# Schematic.net
KiCad netlist of a schematic drawn in EAGLE
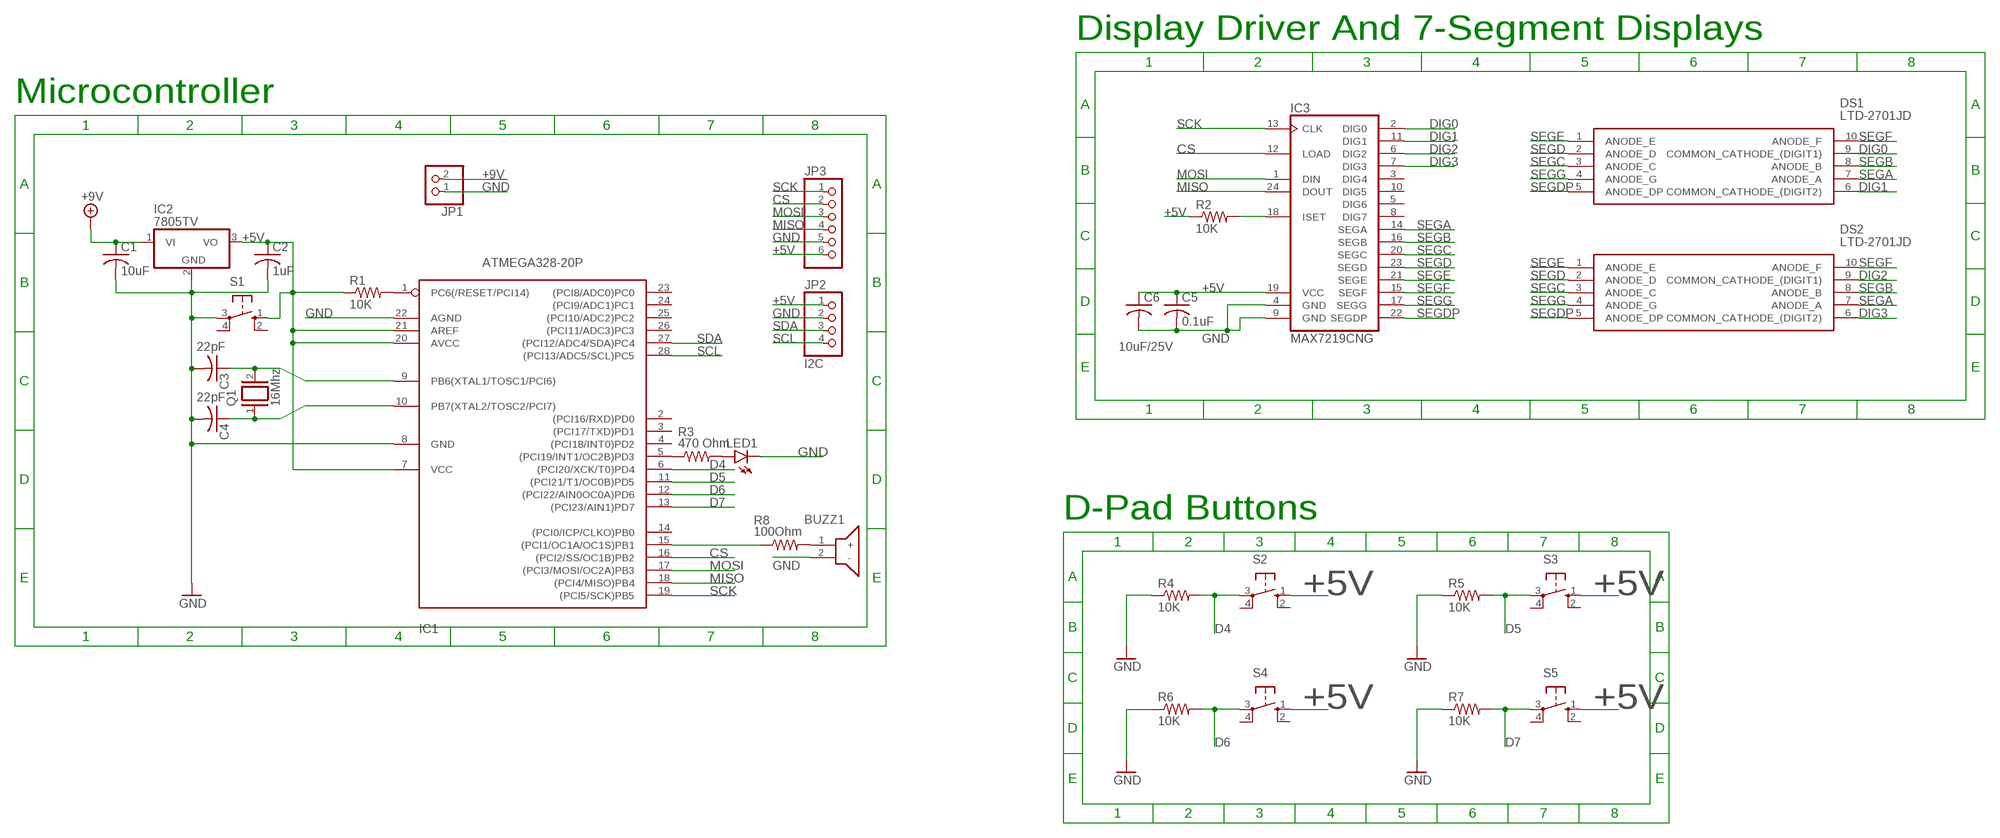
[diagram p0: schematic, sheet 1]

(export (version "E")
  (design (tool "Eeschema 10.0.6"))
  (components
    (comp (ref "BUZZ1")
      (value "CMI-1295-0585T")
      (footprint "eagle-import:CMI12950585T")
      (fields (field (name "MOUSER_PART_NUMBER") "490-CMI-1295-0585T"))
      (libsource (lib "eagle-import") (part "CMI-1295-0585T"))
    )
    (comp (ref "C1")
      (value "10uF")
      (footprint "eagle-import:C1206")
      (libsource (lib "eagle-import") (part "C-USC1206"))
    )
    (comp (ref "C2")
      (value "1uF")
      (footprint "eagle-import:C1206")
      (libsource (lib "eagle-import") (part "C-USC1206"))
    )
    (comp (ref "C3")
      (value "22pF")
      (footprint "eagle-import:C1206")
      (libsource (lib "eagle-import") (part "C-USC1206"))
    )
    (comp (ref "C4")
      (value "22pF")
      (footprint "eagle-import:C1206")
      (libsource (lib "eagle-import") (part "C-USC1206"))
    )
    (comp (ref "C5")
      (value "0.1uF")
      (footprint "eagle-import:C1206")
      (libsource (lib "eagle-import") (part "C-USC1206"))
    )
    (comp (ref "C6")
      (value "10uF/25V")
      (footprint "eagle-import:C1206")
      (libsource (lib "eagle-import") (part "C-USC1206"))
    )
    (comp (ref "DS1")
      (value "LTD-2701JD")
      (footprint "eagle-import:DIPS762W50P254L1502H635Q10N")
      (fields (field (name "MOUSER_PART_NUMBER") "859-LTD-2701JD"))
      (libsource (lib "eagle-import") (part "LTD-2701JD"))
    )
    (comp (ref "DS2")
      (value "LTD-2701JD")
      (footprint "eagle-import:DIPS762W50P254L1502H635Q10N")
      (fields (field (name "MOUSER_PART_NUMBER") "859-LTD-2701JD"))
      (libsource (lib "eagle-import") (part "LTD-2701JD"))
    )
    (comp (ref "IC1")
      (value "ATMEGA328-20P")
      (footprint "eagle-import:DIL28-3")
      (libsource (lib "eagle-import") (part "ATMEGA328P-20"))
    )
    (comp (ref "IC2")
      (value "7805TV")
      (footprint "eagle-import:TO220V")
      (libsource (lib "eagle-import") (part "78TV05"))
    )
    (comp (ref "IC3")
      (value "MAX7219CNG")
      (footprint "eagle-import:DIL24-3")
      (fields (field (name "MF") "MAXIM"))
      (libsource (lib "eagle-import") (part "MAX7219CNG"))
    )
    (comp (ref "JP1")
      (value "PINHD-1X2")
      (footprint "eagle-import:1X02")
      (libsource (lib "eagle-import") (part "PINHD-1X2"))
    )
    (comp (ref "JP2")
      (value "I2C")
      (footprint "eagle-import:1X04")
      (libsource (lib "eagle-import") (part "PINHD-1X4"))
    )
    (comp (ref "JP3")
      (value "PINHD-1X6")
      (footprint "eagle-import:1X06")
      (libsource (lib "eagle-import") (part "PINHD-1X6"))
    )
    (comp (ref "LED1")
      (value "LED5MM")
      (footprint "eagle-import:LED5MM")
      (libsource (lib "eagle-import") (part "LED5MM"))
    )
    (comp (ref "Q1")
      (value "16Mhz")
      (footprint "eagle-import:QS")
      (libsource (lib "eagle-import") (part "XTAL/S"))
    )
    (comp (ref "R1")
      (value "10K")
      (footprint "eagle-import:R1206")
      (libsource (lib "eagle-import") (part "R-US_R1206"))
    )
    (comp (ref "R2")
      (value "10K")
      (footprint "eagle-import:R1206")
      (libsource (lib "eagle-import") (part "R-US_R1206"))
    )
    (comp (ref "R3")
      (value "470 Ohm")
      (footprint "eagle-import:R1206")
      (libsource (lib "eagle-import") (part "R-US_R1206"))
    )
    (comp (ref "R4")
      (value "10K")
      (footprint "eagle-import:R1206")
      (libsource (lib "eagle-import") (part "R-US_R1206"))
    )
    (comp (ref "R5")
      (value "10K")
      (footprint "eagle-import:R1206")
      (libsource (lib "eagle-import") (part "R-US_R1206"))
    )
    (comp (ref "R6")
      (value "10K")
      (footprint "eagle-import:R1206")
      (libsource (lib "eagle-import") (part "R-US_R1206"))
    )
    (comp (ref "R7")
      (value "10K")
      (footprint "eagle-import:R1206")
      (libsource (lib "eagle-import") (part "R-US_R1206"))
    )
    (comp (ref "R8")
      (value "100Ohm")
      (footprint "eagle-import:R1206")
      (libsource (lib "eagle-import") (part "R-US_R1206"))
    )
    (comp (ref "S1")
      (value "10-XX")
      (footprint "eagle-import:B3F-10XX")
      (fields (field (name "MPN") "B3F-1000"))
      (libsource (lib "eagle-import") (part "10-XX"))
    )
    (comp (ref "S2")
      (value "10-XX")
      (footprint "eagle-import:B3F-10XX")
      (fields (field (name "MPN") "B3F-1000"))
      (libsource (lib "eagle-import") (part "10-XX"))
    )
    (comp (ref "S3")
      (value "10-XX")
      (footprint "eagle-import:B3F-10XX")
      (fields (field (name "MPN") "B3F-1000"))
      (libsource (lib "eagle-import") (part "10-XX"))
    )
    (comp (ref "S4")
      (value "10-XX")
      (footprint "eagle-import:B3F-10XX")
      (fields (field (name "MPN") "B3F-1000"))
      (libsource (lib "eagle-import") (part "10-XX"))
    )
    (comp (ref "S5")
      (value "10-XX")
      (footprint "eagle-import:B3F-10XX")
      (fields (field (name "MPN") "B3F-1000"))
      (libsource (lib "eagle-import") (part "10-XX"))
    )
  )
  (nets
    (net (code "1") (name "+9V") (class "Default")
      (node (ref "C1") (pin "1") (pinfunction "1_1") (pintype "passive"))
      (node (ref "IC2") (pin "1") (pinfunction "VI_1") (pintype "input"))
      (node (ref "JP1") (pin "2") (pinfunction "2_2") (pintype "passive"))
    )
    (net (code "2") (name "/+5V") (class "Default")
      (node (ref "C2") (pin "1") (pinfunction "1_1") (pintype "passive"))
      (node (ref "C5") (pin "1") (pinfunction "1_1") (pintype "passive"))
      (node (ref "C6") (pin "1") (pinfunction "1_1") (pintype "passive"))
      (node (ref "IC1") (pin "20") (pinfunction "AVCC_20") (pintype "bidirectional"))
      (node (ref "IC1") (pin "21") (pinfunction "AREF_21") (pintype "bidirectional"))
      (node (ref "IC1") (pin "7") (pinfunction "VCC_7") (pintype "bidirectional"))
      (node (ref "IC2") (pin "3") (pinfunction "VO_3") (pintype "passive"))
      (node (ref "IC3") (pin "19") (pinfunction "VCC_19") (pintype "power_in"))
      (node (ref "JP2") (pin "1") (pinfunction "1_1") (pintype "passive"))
      (node (ref "JP3") (pin "6") (pinfunction "6_6") (pintype "passive"))
      (node (ref "R1") (pin "1") (pinfunction "1_1") (pintype "passive"))
      (node (ref "R2") (pin "1") (pinfunction "1_1") (pintype "passive"))
      (node (ref "S1") (pin "1") (pinfunction "S_1") (pintype "passive"))
      (node (ref "S2") (pin "1") (pinfunction "S_1") (pintype "passive"))
      (node (ref "S3") (pin "1") (pinfunction "S_1") (pintype "passive"))
      (node (ref "S4") (pin "1") (pinfunction "S_1") (pintype "passive"))
      (node (ref "S5") (pin "1") (pinfunction "S_1") (pintype "passive"))
    )
    (net (code "3") (name "/CS") (class "Default")
      (node (ref "IC1") (pin "16") (pinfunction "(PCI2/SS/OC1B)PB2_16") (pintype "bidirectional"))
      (node (ref "IC3") (pin "12") (pinfunction "LOAD_12") (pintype "input"))
      (node (ref "JP3") (pin "2") (pinfunction "2_2") (pintype "passive"))
    )
    (net (code "4") (name "/D4") (class "Default")
      (node (ref "IC1") (pin "6") (pinfunction "(PCI20/XCK/T0)PD4_6") (pintype "bidirectional"))
      (node (ref "R4") (pin "2") (pinfunction "2_2") (pintype "passive"))
      (node (ref "S2") (pin "3") (pinfunction "P_3") (pintype "passive"))
    )
    (net (code "5") (name "/D5") (class "Default")
      (node (ref "IC1") (pin "11") (pinfunction "(PCI21/T1/OC0B)PD5_11") (pintype "bidirectional"))
      (node (ref "R5") (pin "2") (pinfunction "2_2") (pintype "passive"))
      (node (ref "S3") (pin "3") (pinfunction "P_3") (pintype "passive"))
    )
    (net (code "6") (name "/D6") (class "Default")
      (node (ref "IC1") (pin "12") (pinfunction "(PCI22/AIN0OC0A)PD6_12") (pintype "bidirectional"))
      (node (ref "R6") (pin "2") (pinfunction "2_2") (pintype "passive"))
      (node (ref "S4") (pin "3") (pinfunction "P_3") (pintype "passive"))
    )
    (net (code "7") (name "/D7") (class "Default")
      (node (ref "IC1") (pin "13") (pinfunction "(PCI23/AIN1)PD7_13") (pintype "bidirectional"))
      (node (ref "R7") (pin "2") (pinfunction "2_2") (pintype "passive"))
      (node (ref "S5") (pin "3") (pinfunction "P_3") (pintype "passive"))
    )
    (net (code "8") (name "/DIG0") (class "Default")
      (node (ref "DS1") (pin "9") (pinfunction "COMMON_CATHODE_(DIGIT1)_9") (pintype "bidirectional"))
      (node (ref "IC3") (pin "2") (pinfunction "DIG0_2") (pintype "output"))
    )
    (net (code "9") (name "/DIG1") (class "Default")
      (node (ref "DS1") (pin "6") (pinfunction "COMMON_CATHODE_(DIGIT2)_6") (pintype "bidirectional"))
      (node (ref "IC3") (pin "11") (pinfunction "DIG1_11") (pintype "output"))
    )
    (net (code "10") (name "/DIG2") (class "Default")
      (node (ref "DS2") (pin "9") (pinfunction "COMMON_CATHODE_(DIGIT1)_9") (pintype "bidirectional"))
      (node (ref "IC3") (pin "6") (pinfunction "DIG2_6") (pintype "output"))
    )
    (net (code "11") (name "/DIG3") (class "Default")
      (node (ref "DS2") (pin "6") (pinfunction "COMMON_CATHODE_(DIGIT2)_6") (pintype "bidirectional"))
      (node (ref "IC3") (pin "7") (pinfunction "DIG3_7") (pintype "output"))
    )
    (net (code "12") (name "/MISO") (class "Default")
      (node (ref "IC1") (pin "18") (pinfunction "(PCI4/MISO)PB4_18") (pintype "bidirectional"))
      (node (ref "IC3") (pin "24") (pinfunction "DOUT_24") (pintype "output"))
      (node (ref "JP3") (pin "4") (pinfunction "4_4") (pintype "passive"))
    )
    (net (code "13") (name "/MOSI") (class "Default")
      (node (ref "IC1") (pin "17") (pinfunction "(PCI3/MOSI/OC2A)PB3_17") (pintype "bidirectional"))
      (node (ref "IC3") (pin "1") (pinfunction "DIN_1") (pintype "input"))
      (node (ref "JP3") (pin "3") (pinfunction "3_3") (pintype "passive"))
    )
    (net (code "14") (name "/SCK") (class "Default")
      (node (ref "IC1") (pin "19") (pinfunction "(PCI5/SCK)PB5_19") (pintype "bidirectional"))
      (node (ref "IC3") (pin "13") (pinfunction "CLK_13") (pintype "input"))
      (node (ref "JP3") (pin "1") (pinfunction "1_1") (pintype "passive"))
    )
    (net (code "15") (name "/SCL") (class "Default")
      (node (ref "IC1") (pin "28") (pinfunction "(PCI13/ADC5/SCL)PC5_28") (pintype "bidirectional"))
      (node (ref "JP2") (pin "4") (pinfunction "4_4") (pintype "passive"))
    )
    (net (code "16") (name "/SDA") (class "Default")
      (node (ref "IC1") (pin "27") (pinfunction "(PCI12/ADC4/SDA)PC4_27") (pintype "bidirectional"))
      (node (ref "JP2") (pin "3") (pinfunction "3_3") (pintype "passive"))
    )
    (net (code "17") (name "/SEGA") (class "Default")
      (node (ref "DS1") (pin "7") (pinfunction "ANODE_A_7") (pintype "bidirectional"))
      (node (ref "DS2") (pin "7") (pinfunction "ANODE_A_7") (pintype "bidirectional"))
      (node (ref "IC3") (pin "14") (pinfunction "SEGA_14") (pintype "output"))
    )
    (net (code "18") (name "/SEGB") (class "Default")
      (node (ref "DS1") (pin "8") (pinfunction "ANODE_B_8") (pintype "bidirectional"))
      (node (ref "DS2") (pin "8") (pinfunction "ANODE_B_8") (pintype "bidirectional"))
      (node (ref "IC3") (pin "16") (pinfunction "SEGB_16") (pintype "output"))
    )
    (net (code "19") (name "/SEGC") (class "Default")
      (node (ref "DS1") (pin "3") (pinfunction "ANODE_C_3") (pintype "bidirectional"))
      (node (ref "DS2") (pin "3") (pinfunction "ANODE_C_3") (pintype "bidirectional"))
      (node (ref "IC3") (pin "20") (pinfunction "SEGC_20") (pintype "output"))
    )
    (net (code "20") (name "/SEGD") (class "Default")
      (node (ref "DS1") (pin "2") (pinfunction "ANODE_D_2") (pintype "bidirectional"))
      (node (ref "DS2") (pin "2") (pinfunction "ANODE_D_2") (pintype "bidirectional"))
      (node (ref "IC3") (pin "23") (pinfunction "SEGD_23") (pintype "output"))
    )
    (net (code "21") (name "/SEGDP") (class "Default")
      (node (ref "DS1") (pin "5") (pinfunction "ANODE_DP_5") (pintype "bidirectional"))
      (node (ref "DS2") (pin "5") (pinfunction "ANODE_DP_5") (pintype "bidirectional"))
      (node (ref "IC3") (pin "22") (pinfunction "SEGDP_22") (pintype "output"))
    )
    (net (code "22") (name "/SEGE") (class "Default")
      (node (ref "DS1") (pin "1") (pinfunction "ANODE_E_1") (pintype "bidirectional"))
      (node (ref "DS2") (pin "1") (pinfunction "ANODE_E_1") (pintype "bidirectional"))
      (node (ref "IC3") (pin "21") (pinfunction "SEGE_21") (pintype "output"))
    )
    (net (code "23") (name "/SEGF") (class "Default")
      (node (ref "DS1") (pin "10") (pinfunction "ANODE_F_10") (pintype "bidirectional"))
      (node (ref "DS2") (pin "10") (pinfunction "ANODE_F_10") (pintype "bidirectional"))
      (node (ref "IC3") (pin "15") (pinfunction "SEGF_15") (pintype "output"))
    )
    (net (code "24") (name "/SEGG") (class "Default")
      (node (ref "DS1") (pin "4") (pinfunction "ANODE_G_4") (pintype "bidirectional"))
      (node (ref "DS2") (pin "4") (pinfunction "ANODE_G_4") (pintype "bidirectional"))
      (node (ref "IC3") (pin "17") (pinfunction "SEGG_17") (pintype "output"))
    )
    (net (code "25") (name "GND") (class "Default")
      (node (ref "BUZZ1") (pin "2") (pinfunction "-_2") (pintype "bidirectional"))
      (node (ref "C1") (pin "2") (pinfunction "2_2") (pintype "passive"))
      (node (ref "C2") (pin "2") (pinfunction "2_2") (pintype "passive"))
      (node (ref "C3") (pin "2") (pinfunction "2_2") (pintype "passive"))
      (node (ref "C4") (pin "2") (pinfunction "2_2") (pintype "passive"))
      (node (ref "C5") (pin "2") (pinfunction "2_2") (pintype "passive"))
      (node (ref "C6") (pin "2") (pinfunction "2_2") (pintype "passive"))
      (node (ref "IC1") (pin "22") (pinfunction "AGND_22") (pintype "bidirectional"))
      (node (ref "IC1") (pin "8") (pinfunction "GND_8") (pintype "bidirectional"))
      (node (ref "IC2") (pin "2") (pinfunction "GND_2") (pintype "passive"))
      (node (ref "IC3") (pin "4") (pinfunction "GND_4") (pintype "power_in"))
      (node (ref "IC3") (pin "9") (pinfunction "GND_9") (pintype "power_in"))
      (node (ref "JP1") (pin "1") (pinfunction "1_1") (pintype "passive"))
      (node (ref "JP2") (pin "2") (pinfunction "2_2") (pintype "passive"))
      (node (ref "JP3") (pin "5") (pinfunction "5_5") (pintype "passive"))
      (node (ref "LED1") (pin "K") (pinfunction "C_K") (pintype "passive"))
      (node (ref "R4") (pin "1") (pinfunction "1_1") (pintype "passive"))
      (node (ref "R5") (pin "1") (pinfunction "1_1") (pintype "passive"))
      (node (ref "R6") (pin "1") (pinfunction "1_1") (pintype "passive"))
      (node (ref "R7") (pin "1") (pinfunction "1_1") (pintype "passive"))
      (node (ref "S1") (pin "3") (pinfunction "P_3") (pintype "passive"))
    )
    (net (code "26") (name "Net-(BUZZ1-+)") (class "Default")
      (node (ref "BUZZ1") (pin "1") (pinfunction "+_1") (pintype "bidirectional"))
      (node (ref "R8") (pin "2") (pinfunction "2_2") (pintype "passive"))
    )
    (net (code "27") (name "Net-(IC1-(PCI1{slash}OC1A{slash}OC1S)PB1)") (class "Default")
      (node (ref "IC1") (pin "15") (pinfunction "(PCI1/OC1A/OC1S)PB1_15") (pintype "bidirectional"))
      (node (ref "R8") (pin "1") (pinfunction "1_1") (pintype "passive"))
    )
    (net (code "28") (name "Net-(IC1-(PCI19{slash}INT1{slash}OC2B)PD3)") (class "Default")
      (node (ref "IC1") (pin "5") (pinfunction "(PCI19/INT1/OC2B)PD3_5") (pintype "bidirectional"))
      (node (ref "R3") (pin "1") (pinfunction "1_1") (pintype "passive"))
    )
    (net (code "29") (name "Net-(IC1-PB6(XTAL1{slash}TOSC1{slash}PCI6))") (class "Default")
      (node (ref "C3") (pin "1") (pinfunction "1_1") (pintype "passive"))
      (node (ref "IC1") (pin "9") (pinfunction "PB6(XTAL1/TOSC1/PCI6)_9") (pintype "bidirectional"))
      (node (ref "Q1") (pin "2") (pinfunction "2_2") (pintype "passive"))
    )
    (net (code "30") (name "Net-(IC1-PB7(XTAL2{slash}TOSC2{slash}PCI7))") (class "Default")
      (node (ref "C4") (pin "1") (pinfunction "1_1") (pintype "passive"))
      (node (ref "IC1") (pin "10") (pinfunction "PB7(XTAL2/TOSC2/PCI7)_10") (pintype "bidirectional"))
      (node (ref "Q1") (pin "1") (pinfunction "1_1") (pintype "passive"))
    )
    (net (code "31") (name "Net-(IC1-PC6({slash}RESET{slash}PCI14))") (class "Default")
      (node (ref "IC1") (pin "1") (pinfunction "PC6(/RESET/PCI14)_1") (pintype "bidirectional"))
      (node (ref "R1") (pin "2") (pinfunction "2_2") (pintype "passive"))
    )
    (net (code "32") (name "Net-(IC3-ISET)") (class "Default")
      (node (ref "IC3") (pin "18") (pinfunction "ISET_18") (pintype "input"))
      (node (ref "R2") (pin "2") (pinfunction "2_2") (pintype "passive"))
    )
    (net (code "33") (name "Net-(LED1-PadA)") (class "Default")
      (node (ref "LED1") (pin "A") (pinfunction "A_A") (pintype "passive"))
      (node (ref "R3") (pin "2") (pinfunction "2_2") (pintype "passive"))
    )
    (net (code "34") (name "unconnected-(IC1-(PCI0{slash}ICP{slash}CLKO)PB0-Pad14)") (class "Default")
      (node (ref "IC1") (pin "14") (pinfunction "(PCI0/ICP/CLKO)PB0_14") (pintype "bidirectional"))
    )
    (net (code "35") (name "unconnected-(IC1-(PCI8{slash}ADC0)PC0-Pad23)") (class "Default")
      (node (ref "IC1") (pin "23") (pinfunction "(PCI8/ADC0)PC0_23") (pintype "bidirectional"))
    )
    (net (code "36") (name "unconnected-(IC1-(PCI9{slash}ADC1)PC1-Pad24)") (class "Default")
      (node (ref "IC1") (pin "24") (pinfunction "(PCI9/ADC1)PC1_24") (pintype "bidirectional"))
    )
    (net (code "37") (name "unconnected-(IC1-(PCI10{slash}ADC2)PC2-Pad25)") (class "Default")
      (node (ref "IC1") (pin "25") (pinfunction "(PCI10/ADC2)PC2_25") (pintype "bidirectional"))
    )
    (net (code "38") (name "unconnected-(IC1-(PCI11{slash}ADC3)PC3-Pad26)") (class "Default")
      (node (ref "IC1") (pin "26") (pinfunction "(PCI11/ADC3)PC3_26") (pintype "bidirectional"))
    )
    (net (code "39") (name "unconnected-(IC1-(PCI16{slash}RXD)PD0-Pad2)") (class "Default")
      (node (ref "IC1") (pin "2") (pinfunction "(PCI16/RXD)PD0_2") (pintype "bidirectional"))
    )
    (net (code "40") (name "unconnected-(IC1-(PCI17{slash}TXD)PD1-Pad3)") (class "Default")
      (node (ref "IC1") (pin "3") (pinfunction "(PCI17/TXD)PD1_3") (pintype "bidirectional"))
    )
    (net (code "41") (name "unconnected-(IC1-(PCI18{slash}INT0)PD2-Pad4)") (class "Default")
      (node (ref "IC1") (pin "4") (pinfunction "(PCI18/INT0)PD2_4") (pintype "bidirectional"))
    )
    (net (code "42") (name "unconnected-(IC3-DIG4-Pad3)") (class "Default")
      (node (ref "IC3") (pin "3") (pinfunction "DIG4_3") (pintype "output"))
    )
    (net (code "43") (name "unconnected-(IC3-DIG5-Pad10)") (class "Default")
      (node (ref "IC3") (pin "10") (pinfunction "DIG5_10") (pintype "output"))
    )
    (net (code "44") (name "unconnected-(IC3-DIG6-Pad5)") (class "Default")
      (node (ref "IC3") (pin "5") (pinfunction "DIG6_5") (pintype "output"))
    )
    (net (code "45") (name "unconnected-(IC3-DIG7-Pad8)") (class "Default")
      (node (ref "IC3") (pin "8") (pinfunction "DIG7_8") (pintype "output"))
    )
    (net (code "46") (name "unconnected-(S1-P1-Pad4)") (class "Default")
      (node (ref "S1") (pin "4") (pinfunction "P1_4") (pintype "passive"))
    )
    (net (code "47") (name "unconnected-(S1-S1-Pad2)") (class "Default")
      (node (ref "S1") (pin "2") (pinfunction "S1_2") (pintype "passive"))
    )
    (net (code "48") (name "unconnected-(S2-P1-Pad4)") (class "Default")
      (node (ref "S2") (pin "4") (pinfunction "P1_4") (pintype "passive"))
    )
    (net (code "49") (name "unconnected-(S2-S1-Pad2)") (class "Default")
      (node (ref "S2") (pin "2") (pinfunction "S1_2") (pintype "passive"))
    )
    (net (code "50") (name "unconnected-(S3-P1-Pad4)") (class "Default")
      (node (ref "S3") (pin "4") (pinfunction "P1_4") (pintype "passive"))
    )
    (net (code "51") (name "unconnected-(S3-S1-Pad2)") (class "Default")
      (node (ref "S3") (pin "2") (pinfunction "S1_2") (pintype "passive"))
    )
    (net (code "52") (name "unconnected-(S4-P1-Pad4)") (class "Default")
      (node (ref "S4") (pin "4") (pinfunction "P1_4") (pintype "passive"))
    )
    (net (code "53") (name "unconnected-(S4-S1-Pad2)") (class "Default")
      (node (ref "S4") (pin "2") (pinfunction "S1_2") (pintype "passive"))
    )
    (net (code "54") (name "unconnected-(S5-P1-Pad4)") (class "Default")
      (node (ref "S5") (pin "4") (pinfunction "P1_4") (pintype "passive"))
    )
    (net (code "55") (name "unconnected-(S5-S1-Pad2)") (class "Default")
      (node (ref "S5") (pin "2") (pinfunction "S1_2") (pintype "passive"))
    )
  )
)
